# SNES_RGBAmp.net
KiCad netlist of a schematic drawn in EAGLE
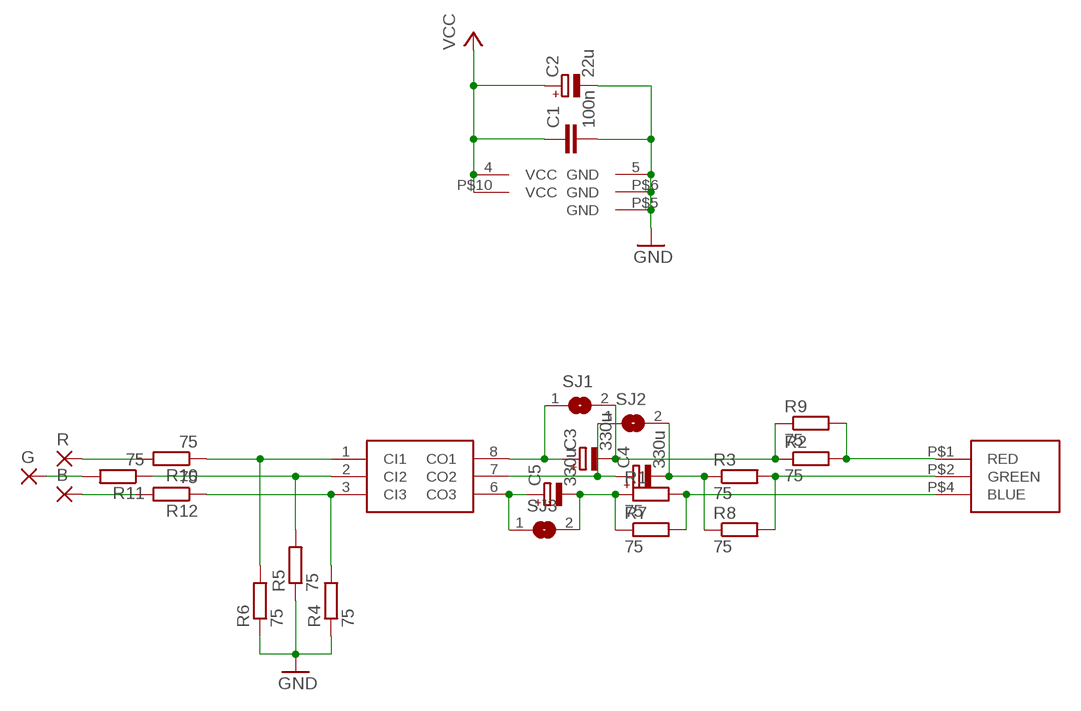
[diagram p0: schematic, sheet 1]

(export (version "E")
  (design (tool "Eeschema 10.0.6"))
  (components
    (comp (ref "B")
      (value "SMD2")
      (footprint "eagle-import:SMD1,27-2,54")
      (libsource (lib "eagle-import") (part "SMD2"))
    )
    (comp (ref "C1")
      (value "100n")
      (footprint "eagle-import:Z0805")
      (libsource (lib "eagle-import") (part "C0805"))
    )
    (comp (ref "C2")
      (value "22u")
      (footprint "eagle-import:SMC_C")
      (libsource (lib "eagle-import") (part "CPOL-EUSMCC"))
    )
    (comp (ref "C3")
      (value "330u")
      (footprint "eagle-import:SMC_D")
      (libsource (lib "eagle-import") (part "CPOL-EUSMCD"))
    )
    (comp (ref "C4")
      (value "330u")
      (footprint "eagle-import:SMC_D")
      (libsource (lib "eagle-import") (part "CPOL-EUSMCD"))
    )
    (comp (ref "C5")
      (value "330u")
      (footprint "eagle-import:SMC_D")
      (libsource (lib "eagle-import") (part "CPOL-EUSMCD"))
    )
    (comp (ref "G")
      (value "SMD2")
      (footprint "eagle-import:SMD1,27-2,54")
      (libsource (lib "eagle-import") (part "SMD2"))
    )
    (comp (ref "R")
      (value "SMD2")
      (footprint "eagle-import:SMD1,27-2,54")
      (libsource (lib "eagle-import") (part "SMD2"))
    )
    (comp (ref "R1")
      (value "75")
      (footprint "eagle-import:Z0805")
      (libsource (lib "eagle-import") (part "R0805"))
    )
    (comp (ref "R2")
      (value "75")
      (footprint "eagle-import:Z0805")
      (libsource (lib "eagle-import") (part "R0805"))
    )
    (comp (ref "R3")
      (value "75")
      (footprint "eagle-import:Z0805")
      (libsource (lib "eagle-import") (part "R0805"))
    )
    (comp (ref "R4")
      (value "75")
      (footprint "eagle-import:Z0805")
      (libsource (lib "eagle-import") (part "R0805"))
    )
    (comp (ref "R5")
      (value "75")
      (footprint "eagle-import:Z0805")
      (libsource (lib "eagle-import") (part "R0805"))
    )
    (comp (ref "R6")
      (value "75")
      (footprint "eagle-import:Z0805")
      (libsource (lib "eagle-import") (part "R0805"))
    )
    (comp (ref "R7")
      (value "75")
      (footprint "eagle-import:Z0805")
      (libsource (lib "eagle-import") (part "R0805"))
    )
    (comp (ref "R8")
      (value "75")
      (footprint "eagle-import:Z0805")
      (libsource (lib "eagle-import") (part "R0805"))
    )
    (comp (ref "R9")
      (value "75")
      (footprint "eagle-import:Z0805")
      (libsource (lib "eagle-import") (part "R0805"))
    )
    (comp (ref "R10")
      (value "75")
      (footprint "eagle-import:Z0805")
      (libsource (lib "eagle-import") (part "R0805"))
    )
    (comp (ref "R11")
      (value "75")
      (footprint "eagle-import:Z0805")
      (libsource (lib "eagle-import") (part "R0805"))
    )
    (comp (ref "R12")
      (value "75")
      (footprint "eagle-import:Z0805")
      (libsource (lib "eagle-import") (part "R0805"))
    )
    (comp (ref "SJ1") (value "SJ") (footprint "eagle-import:SJ") (libsource (lib "eagle-import") (part "SJ")))
    (comp (ref "SJ2") (value "SJ") (footprint "eagle-import:SJ") (libsource (lib "eagle-import") (part "SJ")))
    (comp (ref "SJ3") (value "SJ") (footprint "eagle-import:SJ") (libsource (lib "eagle-import") (part "SJ")))
    (comp (ref "U$1")
      (value "THS7314")
      (footprint "eagle-import:THS7314")
      (libsource (lib "eagle-import") (part "THS7314"))
    )
    (comp (ref "U$2")
      (value "SNES_MULTIAV_RGB_ONLY")
      (footprint "eagle-import:SNES_MULTIAV_RGB_ONLY")
      (libsource (lib "eagle-import") (part "SNES_MULTIAV_RGB_ONLY"))
    )
  )
  (nets
    (net (code "1") (name "GND") (class "Default")
      (node (ref "C1") (pin "2") (pinfunction "2_2") (pintype "passive"))
      (node (ref "C2") (pin "-") (pinfunction "-_-") (pintype "passive"))
      (node (ref "R4") (pin "1") (pinfunction "1_1") (pintype "passive"))
      (node (ref "R5") (pin "1") (pinfunction "1_1") (pintype "passive"))
      (node (ref "R6") (pin "1") (pinfunction "1_1") (pintype "passive"))
      (node (ref "U$1") (pin "5") (pinfunction "GND_5") (pintype "bidirectional"))
      (node (ref "U$2") (pin "P$5") (pinfunction "GND_P$5") (pintype "bidirectional"))
      (node (ref "U$2") (pin "P$6") (pinfunction "GND_P$6") (pintype "bidirectional"))
    )
    (net (code "2") (name "Net-(B-P)") (class "Default")
      (node (ref "B") (pin "1") (pinfunction "P_1") (pintype "passive"))
      (node (ref "R12") (pin "2") (pinfunction "2_2") (pintype "passive"))
    )
    (net (code "3") (name "Net-(C3-Pad-)") (class "Default")
      (node (ref "C3") (pin "-") (pinfunction "-_-") (pintype "passive"))
      (node (ref "R2") (pin "1") (pinfunction "1_1") (pintype "passive"))
      (node (ref "R9") (pin "1") (pinfunction "1_1") (pintype "passive"))
      (node (ref "SJ1") (pin "2") (pinfunction "2_2") (pintype "passive"))
    )
    (net (code "4") (name "Net-(C4-Pad-)") (class "Default")
      (node (ref "C4") (pin "-") (pinfunction "-_-") (pintype "passive"))
      (node (ref "R3") (pin "1") (pinfunction "1_1") (pintype "passive"))
      (node (ref "R8") (pin "1") (pinfunction "1_1") (pintype "passive"))
      (node (ref "SJ2") (pin "2") (pinfunction "2_2") (pintype "passive"))
    )
    (net (code "5") (name "Net-(C5-Pad-)") (class "Default")
      (node (ref "C5") (pin "-") (pinfunction "-_-") (pintype "passive"))
      (node (ref "R1") (pin "1") (pinfunction "1_1") (pintype "passive"))
      (node (ref "R7") (pin "1") (pinfunction "1_1") (pintype "passive"))
      (node (ref "SJ3") (pin "2") (pinfunction "2_2") (pintype "passive"))
    )
    (net (code "6") (name "Net-(G-P)") (class "Default")
      (node (ref "G") (pin "1") (pinfunction "P_1") (pintype "passive"))
      (node (ref "R11") (pin "2") (pinfunction "2_2") (pintype "passive"))
    )
    (net (code "7") (name "Net-(R-P)") (class "Default")
      (node (ref "R") (pin "1") (pinfunction "P_1") (pintype "passive"))
      (node (ref "R10") (pin "2") (pinfunction "2_2") (pintype "passive"))
    )
    (net (code "8") (name "Net-(U$1A-CI1)") (class "Default")
      (node (ref "R10") (pin "1") (pinfunction "1_1") (pintype "passive"))
      (node (ref "R6") (pin "2") (pinfunction "2_2") (pintype "passive"))
      (node (ref "U$1") (pin "1") (pinfunction "CI1_1") (pintype "bidirectional"))
    )
    (net (code "9") (name "Net-(U$1A-CI2)") (class "Default")
      (node (ref "R11") (pin "1") (pinfunction "1_1") (pintype "passive"))
      (node (ref "R5") (pin "2") (pinfunction "2_2") (pintype "passive"))
      (node (ref "U$1") (pin "2") (pinfunction "CI2_2") (pintype "bidirectional"))
    )
    (net (code "10") (name "Net-(U$1A-CI3)") (class "Default")
      (node (ref "R12") (pin "1") (pinfunction "1_1") (pintype "passive"))
      (node (ref "R4") (pin "2") (pinfunction "2_2") (pintype "passive"))
      (node (ref "U$1") (pin "3") (pinfunction "CI3_3") (pintype "bidirectional"))
    )
    (net (code "11") (name "Net-(U$1A-CO1)") (class "Default")
      (node (ref "C3") (pin "+") (pinfunction "+_+") (pintype "passive"))
      (node (ref "SJ1") (pin "1") (pinfunction "1_1") (pintype "passive"))
      (node (ref "U$1") (pin "8") (pinfunction "CO1_8") (pintype "bidirectional"))
    )
    (net (code "12") (name "Net-(U$1A-CO2)") (class "Default")
      (node (ref "C4") (pin "+") (pinfunction "+_+") (pintype "passive"))
      (node (ref "SJ2") (pin "1") (pinfunction "1_1") (pintype "passive"))
      (node (ref "U$1") (pin "7") (pinfunction "CO2_7") (pintype "bidirectional"))
    )
    (net (code "13") (name "Net-(U$1A-CO3)") (class "Default")
      (node (ref "C5") (pin "+") (pinfunction "+_+") (pintype "passive"))
      (node (ref "SJ3") (pin "1") (pinfunction "1_1") (pintype "passive"))
      (node (ref "U$1") (pin "6") (pinfunction "CO3_6") (pintype "bidirectional"))
    )
    (net (code "14") (name "Net-(U$2C-BLUE)") (class "Default")
      (node (ref "R1") (pin "2") (pinfunction "2_2") (pintype "passive"))
      (node (ref "R7") (pin "2") (pinfunction "2_2") (pintype "passive"))
      (node (ref "U$2") (pin "P$4") (pinfunction "BLUE_P$4") (pintype "bidirectional"))
    )
    (net (code "15") (name "Net-(U$2C-GREEN)") (class "Default")
      (node (ref "R3") (pin "2") (pinfunction "2_2") (pintype "passive"))
      (node (ref "R8") (pin "2") (pinfunction "2_2") (pintype "passive"))
      (node (ref "U$2") (pin "P$2") (pinfunction "GREEN_P$2") (pintype "bidirectional"))
    )
    (net (code "16") (name "Net-(U$2C-RED)") (class "Default")
      (node (ref "R2") (pin "2") (pinfunction "2_2") (pintype "passive"))
      (node (ref "R9") (pin "2") (pinfunction "2_2") (pintype "passive"))
      (node (ref "U$2") (pin "P$1") (pinfunction "RED_P$1") (pintype "bidirectional"))
    )
    (net (code "17") (name "VCC") (class "Default")
      (node (ref "C1") (pin "1") (pinfunction "1_1") (pintype "passive"))
      (node (ref "C2") (pin "+") (pinfunction "+_+") (pintype "passive"))
      (node (ref "U$1") (pin "4") (pinfunction "VCC_4") (pintype "bidirectional"))
      (node (ref "U$2") (pin "P$10") (pinfunction "VCC_P$10") (pintype "bidirectional"))
    )
  )
)
